# bene2stmbl-smd.net
KiCad netlist of a schematic drawn in EAGLE
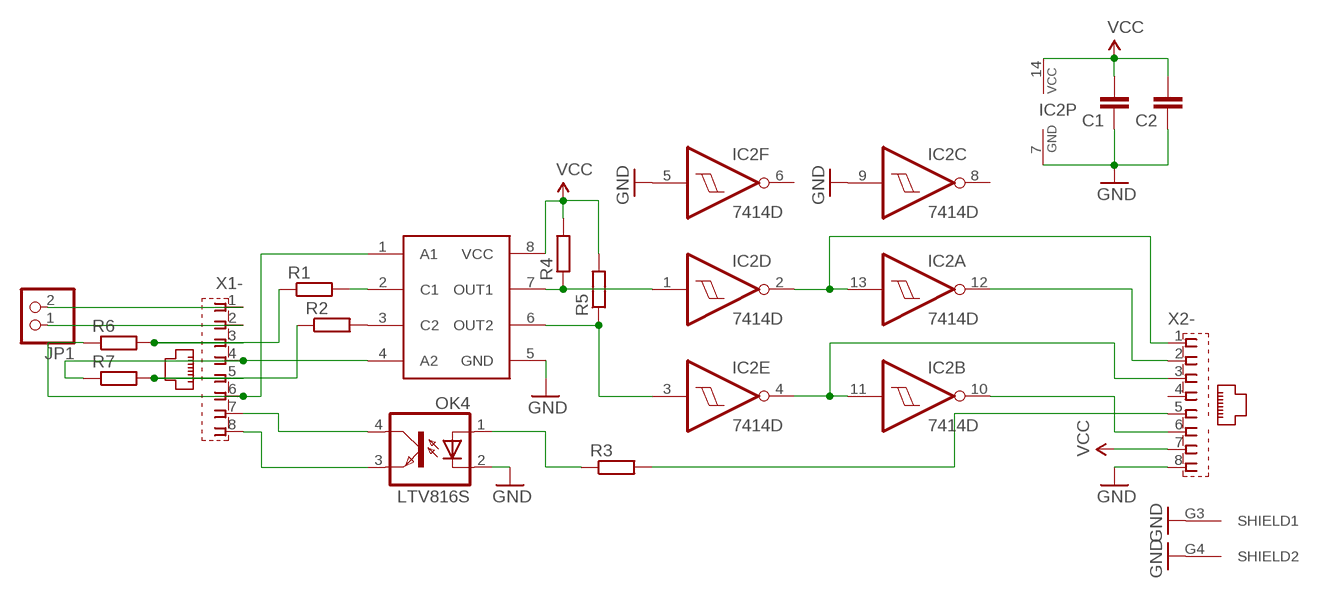
[diagram p0: schematic, sheet 1]

(export (version "E")
  (design (tool "Eeschema 10.0.6"))
  (components
    (comp (ref "C1")
      (value "C-EUC0603")
      (footprint "eagle-import:C0603")
      (libsource (lib "eagle-import") (part "C-EUC0603"))
    )
    (comp (ref "C2")
      (value "C-EUC0603")
      (footprint "eagle-import:C0603")
      (libsource (lib "eagle-import") (part "C-EUC0603"))
    )
    (comp (ref "IC2")
      (value "7414D")
      (footprint "eagle-import:SO14")
      (libsource (lib "eagle-import") (part "7414D"))
    )
    (comp (ref "JP1")
      (value "PINHD-1X2")
      (footprint "eagle-import:1X02")
      (libsource (lib "eagle-import") (part "PINHD-1X2"))
    )
    (comp (ref "OK4")
      (value "LTV816S")
      (footprint "eagle-import:SMD4")
      (libsource (lib "eagle-import") (part "LTV816S"))
    )
    (comp (ref "R1")
      (value "R-EU_R0603")
      (footprint "eagle-import:R0603")
      (libsource (lib "eagle-import") (part "R-EU_R0603"))
    )
    (comp (ref "R2")
      (value "R-EU_R0603")
      (footprint "eagle-import:R0603")
      (libsource (lib "eagle-import") (part "R-EU_R0603"))
    )
    (comp (ref "R3")
      (value "R-EU_R0603")
      (footprint "eagle-import:R0603")
      (libsource (lib "eagle-import") (part "R-EU_R0603"))
    )
    (comp (ref "R4")
      (value "R-EU_R0603")
      (footprint "eagle-import:R0603")
      (libsource (lib "eagle-import") (part "R-EU_R0603"))
    )
    (comp (ref "R5")
      (value "R-EU_R0603")
      (footprint "eagle-import:R0603")
      (libsource (lib "eagle-import") (part "R-EU_R0603"))
    )
    (comp (ref "R6")
      (value "R-EU_R0603")
      (footprint "eagle-import:R0603")
      (libsource (lib "eagle-import") (part "R-EU_R0603"))
    )
    (comp (ref "R7")
      (value "R-EU_R0603")
      (footprint "eagle-import:R0603")
      (libsource (lib "eagle-import") (part "R-EU_R0603"))
    )
    (comp (ref "U$1")
      (value "HCPL-053L-SMD")
      (footprint "eagle-import:SO08")
      (libsource (lib "eagle-import") (part "HCPL-053L-SMD"))
    )
    (comp (ref "X1")
      (value "RJ45")
      (footprint "eagle-import:RJ45")
      (libsource (lib "eagle-import") (part "RJ45"))
    )
    (comp (ref "X2")
      (value "RJ45")
      (footprint "eagle-import:RJ45")
      (libsource (lib "eagle-import") (part "RJ45"))
    )
  )
  (nets
    (net (code "1") (name "GND") (class "Default")
      (node (ref "C1") (pin "1") (pinfunction "1_1") (pintype "passive"))
      (node (ref "C2") (pin "1") (pinfunction "1_1") (pintype "passive"))
      (node (ref "IC2") (pin "5") (pinfunction "I_5") (pintype "input"))
      (node (ref "IC2") (pin "7") (pinfunction "GND_7") (pintype "power_in"))
      (node (ref "IC2") (pin "9") (pinfunction "I_9") (pintype "input"))
      (node (ref "OK4") (pin "2") (pinfunction "C_2") (pintype "passive"))
      (node (ref "U$1") (pin "5") (pinfunction "GND_5") (pintype "bidirectional"))
      (node (ref "X2") (pin "8") (pinfunction "8_8") (pintype "passive"))
      (node (ref "X2") (pin "G3") (pinfunction "SHIELD1_G3") (pintype "bidirectional"))
      (node (ref "X2") (pin "G4") (pinfunction "SHIELD2_G4") (pintype "bidirectional"))
    )
    (net (code "2") (name "Net-(IC2A-I)") (class "Default")
      (node (ref "IC2") (pin "13") (pinfunction "I_13") (pintype "input"))
      (node (ref "IC2") (pin "2") (pinfunction "O_2") (pintype "output"))
      (node (ref "X2") (pin "1") (pinfunction "1_1") (pintype "passive"))
    )
    (net (code "3") (name "Net-(IC2A-O)") (class "Default")
      (node (ref "IC2") (pin "12") (pinfunction "O_12") (pintype "output"))
      (node (ref "X2") (pin "2") (pinfunction "2_2") (pintype "passive"))
    )
    (net (code "4") (name "Net-(IC2B-I)") (class "Default")
      (node (ref "IC2") (pin "11") (pinfunction "I_11") (pintype "input"))
      (node (ref "IC2") (pin "4") (pinfunction "O_4") (pintype "output"))
      (node (ref "X2") (pin "3") (pinfunction "3_3") (pintype "passive"))
    )
    (net (code "5") (name "Net-(IC2B-O)") (class "Default")
      (node (ref "IC2") (pin "10") (pinfunction "O_10") (pintype "output"))
      (node (ref "X2") (pin "6") (pinfunction "6_6") (pintype "passive"))
    )
    (net (code "6") (name "Net-(IC2D-I)") (class "Default")
      (node (ref "IC2") (pin "1") (pinfunction "I_1") (pintype "input"))
      (node (ref "R4") (pin "1") (pinfunction "1_1") (pintype "passive"))
      (node (ref "U$1") (pin "7") (pinfunction "OUT1_7") (pintype "bidirectional"))
    )
    (net (code "7") (name "Net-(IC2E-I)") (class "Default")
      (node (ref "IC2") (pin "3") (pinfunction "I_3") (pintype "input"))
      (node (ref "R5") (pin "1") (pinfunction "1_1") (pintype "passive"))
      (node (ref "U$1") (pin "6") (pinfunction "OUT2_6") (pintype "bidirectional"))
    )
    (net (code "8") (name "Net-(JP1-Pad1)") (class "Default")
      (node (ref "JP1") (pin "1") (pinfunction "1_1") (pintype "passive"))
      (node (ref "X1") (pin "2") (pinfunction "2_2") (pintype "passive"))
    )
    (net (code "9") (name "Net-(JP1-Pad2)") (class "Default")
      (node (ref "JP1") (pin "2") (pinfunction "2_2") (pintype "passive"))
      (node (ref "X1") (pin "1") (pinfunction "1_1") (pintype "passive"))
    )
    (net (code "10") (name "Net-(OK4-A)") (class "Default")
      (node (ref "OK4") (pin "1") (pinfunction "A_1") (pintype "passive"))
      (node (ref "R3") (pin "1") (pinfunction "1_1") (pintype "passive"))
    )
    (net (code "11") (name "Net-(OK4-COL)") (class "Default")
      (node (ref "OK4") (pin "4") (pinfunction "COL_4") (pintype "passive"))
      (node (ref "X1") (pin "7") (pinfunction "7_7") (pintype "passive"))
    )
    (net (code "12") (name "Net-(OK4-EMIT)") (class "Default")
      (node (ref "OK4") (pin "3") (pinfunction "EMIT_3") (pintype "passive"))
      (node (ref "X1") (pin "8") (pinfunction "8_8") (pintype "passive"))
    )
    (net (code "13") (name "Net-(R1-Pad1)") (class "Default")
      (node (ref "R1") (pin "1") (pinfunction "1_1") (pintype "passive"))
      (node (ref "R6") (pin "2") (pinfunction "2_2") (pintype "passive"))
      (node (ref "X1") (pin "3") (pinfunction "3_3") (pintype "passive"))
    )
    (net (code "14") (name "Net-(R2-Pad1)") (class "Default")
      (node (ref "R2") (pin "1") (pinfunction "1_1") (pintype "passive"))
      (node (ref "R7") (pin "2") (pinfunction "2_2") (pintype "passive"))
      (node (ref "X1") (pin "5") (pinfunction "5_5") (pintype "passive"))
    )
    (net (code "15") (name "Net-(R3-Pad2)") (class "Default")
      (node (ref "R3") (pin "2") (pinfunction "2_2") (pintype "passive"))
      (node (ref "X2") (pin "5") (pinfunction "5_5") (pintype "passive"))
    )
    (net (code "16") (name "Net-(U$1-A1)") (class "Default")
      (node (ref "R6") (pin "1") (pinfunction "1_1") (pintype "passive"))
      (node (ref "U$1") (pin "1") (pinfunction "A1_1") (pintype "bidirectional"))
      (node (ref "X1") (pin "6") (pinfunction "6_6") (pintype "passive"))
    )
    (net (code "17") (name "Net-(U$1-A2)") (class "Default")
      (node (ref "R7") (pin "1") (pinfunction "1_1") (pintype "passive"))
      (node (ref "U$1") (pin "4") (pinfunction "A2_4") (pintype "bidirectional"))
      (node (ref "X1") (pin "4") (pinfunction "4_4") (pintype "passive"))
    )
    (net (code "18") (name "Net-(U$1-C1)") (class "Default")
      (node (ref "R1") (pin "2") (pinfunction "2_2") (pintype "passive"))
      (node (ref "U$1") (pin "2") (pinfunction "C1_2") (pintype "bidirectional"))
    )
    (net (code "19") (name "Net-(U$1-C2)") (class "Default")
      (node (ref "R2") (pin "2") (pinfunction "2_2") (pintype "passive"))
      (node (ref "U$1") (pin "3") (pinfunction "C2_3") (pintype "bidirectional"))
    )
    (net (code "20") (name "VCC") (class "Default")
      (node (ref "C1") (pin "2") (pinfunction "2_2") (pintype "passive"))
      (node (ref "C2") (pin "2") (pinfunction "2_2") (pintype "passive"))
      (node (ref "IC2") (pin "14") (pinfunction "VCC_14") (pintype "power_in"))
      (node (ref "R4") (pin "2") (pinfunction "2_2") (pintype "passive"))
      (node (ref "R5") (pin "2") (pinfunction "2_2") (pintype "passive"))
      (node (ref "U$1") (pin "8") (pinfunction "VCC_8") (pintype "bidirectional"))
      (node (ref "X2") (pin "7") (pinfunction "7_7") (pintype "passive"))
    )
    (net (code "21") (name "unconnected-(IC2C-O-Pad8)") (class "Default")
      (node (ref "IC2") (pin "8") (pinfunction "O_8") (pintype "output"))
    )
    (net (code "22") (name "unconnected-(IC2F-O-Pad6)") (class "Default")
      (node (ref "IC2") (pin "6") (pinfunction "O_6") (pintype "output"))
    )
    (net (code "23") (name "unconnected-(X2-Pad4)") (class "Default")
      (node (ref "X2") (pin "4") (pinfunction "4_4") (pintype "passive"))
    )
  )
)
